# PIR_new.net
KiCad netlist of a schematic drawn in EAGLE
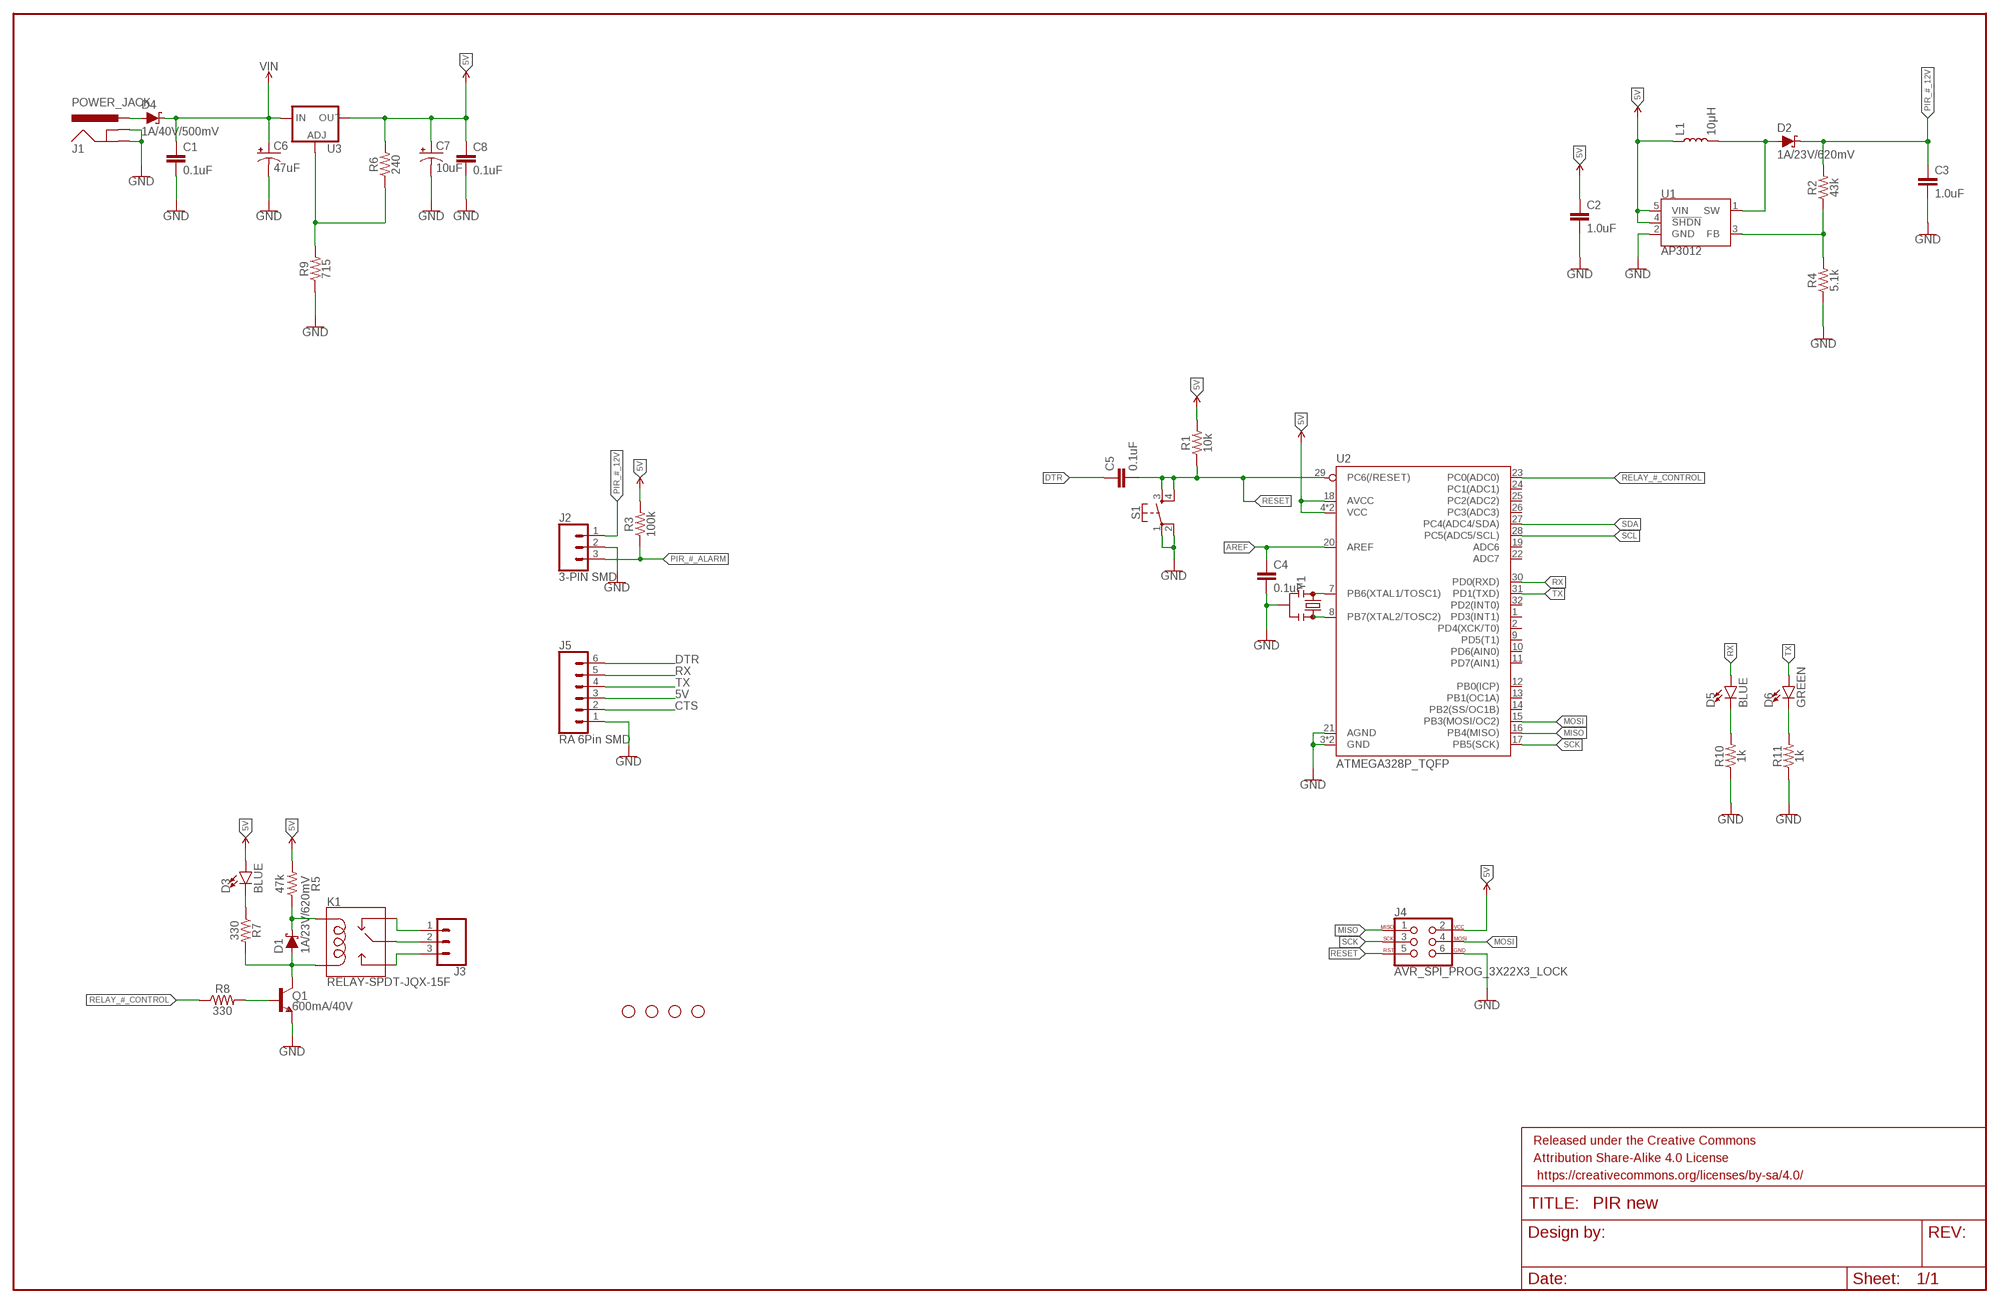
[diagram p0: schematic, sheet 1]

(export (version "E")
  (design (tool "Eeschema 10.0.6"))
  (components
    (comp (ref "C1")
      (value "0.1uF")
      (footprint "eagle-import:0603")
      (libsource (lib "eagle-import") (part "SparkFun-Capacitors_510_0.1UF-0603-25V-5%"))
    )
    (comp (ref "C2")
      (value "1.0uF")
      (footprint "eagle-import:0603")
      (libsource (lib "eagle-import") (part "1.0UF-0603-16V-10%"))
    )
    (comp (ref "C3")
      (value "1.0uF")
      (footprint "eagle-import:0603")
      (libsource (lib "eagle-import") (part "1.0UF-0603-16V-10%"))
    )
    (comp (ref "C4")
      (value "0.1uF")
      (footprint "eagle-import:0603")
      (libsource (lib "eagle-import") (part "0.1UF-0603-25V-(+80/-20%)"))
    )
    (comp (ref "C5")
      (value "0.1uF")
      (footprint "eagle-import:0603")
      (libsource (lib "eagle-import") (part "0.1UF-0603-25V-(+80/-20%)"))
    )
    (comp (ref "C6")
      (value "47uF")
      (footprint "eagle-import:PANASONIC_D")
      (libsource (lib "eagle-import") (part "47UF-POLAR-PANASONIC_D-35V-20%"))
    )
    (comp (ref "C7")
      (value "10uF")
      (footprint "eagle-import:EIA3216")
      (libsource (lib "eagle-import") (part "10UF-POLAR-EIA3216-16V-10%(TANT)"))
    )
    (comp (ref "C8")
      (value "0.1uF")
      (footprint "eagle-import:0603")
      (libsource (lib "eagle-import") (part "0.1UF-0603-25V-(+80/-20%)"))
    )
    (comp (ref "D1")
      (value "1A/23V/620mV")
      (footprint "eagle-import:SOD-323")
      (libsource (lib "eagle-import") (part "DIODE-SCHOTTKY-BAT20J"))
    )
    (comp (ref "D2")
      (value "1A/23V/620mV")
      (footprint "eagle-import:SOD-323")
      (libsource (lib "eagle-import") (part "DIODE-SCHOTTKY-BAT20J"))
    )
    (comp (ref "D3")
      (value "BLUE")
      (footprint "eagle-import:LED-0603")
      (libsource (lib "eagle-import") (part "LED-BLUE0603"))
    )
    (comp (ref "D4")
      (value "1A/40V/500mV")
      (footprint "eagle-import:SMA-DIODE")
      (libsource (lib "eagle-import") (part "DIODE-SCHOTTKY-SS14"))
    )
    (comp (ref "D5")
      (value "BLUE")
      (footprint "eagle-import:LED-0603")
      (libsource (lib "eagle-import") (part "LED-BLUE0603"))
    )
    (comp (ref "D6")
      (value "GREEN")
      (footprint "eagle-import:LED-0603")
      (libsource (lib "eagle-import") (part "LED-GREEN0603"))
    )
    (comp (ref "FRAME1")
      (value "FRAME-LEDGER")
      (footprint "eagle-import:CREATIVE_COMMONS")
      (libsource (lib "eagle-import") (part "FRAME-LEDGER"))
    )
    (comp (ref "H1")
      (value "STAND-OFF")
      (footprint "eagle-import:STAND-OFF")
      (libsource (lib "eagle-import") (part "STAND-OFF"))
    )
    (comp (ref "H2")
      (value "STAND-OFF")
      (footprint "eagle-import:STAND-OFF")
      (libsource (lib "eagle-import") (part "STAND-OFF"))
    )
    (comp (ref "H3")
      (value "STAND-OFF")
      (footprint "eagle-import:STAND-OFF")
      (libsource (lib "eagle-import") (part "STAND-OFF"))
    )
    (comp (ref "H4")
      (value "STAND-OFF")
      (footprint "eagle-import:STAND-OFF")
      (libsource (lib "eagle-import") (part "STAND-OFF"))
    )
    (comp (ref "J1")
      (value "POWER_JACK")
      (footprint "eagle-import:POWER_JACK_PTH")
      (libsource (lib "eagle-import") (part "POWER_JACK"))
    )
    (comp (ref "J2")
      (value "3-PIN SMD")
      (footprint "eagle-import:JST-3-SMD")
      (libsource (lib "eagle-import") (part "CONN_03JST-SMD"))
    )
    (comp (ref "J3")
      (value "CONN_03SCREW_LOCK")
      (footprint "eagle-import:SCREWTERMINAL-3.5MM-3_LOCK.007S")
      (libsource (lib "eagle-import") (part "CONN_03SCREW_LOCK"))
    )
    (comp (ref "J4")
      (value "AVR_SPI_PROG_3X22X3_LOCK")
      (footprint "eagle-import:2X3_LOCK")
      (libsource (lib "eagle-import") (part "AVR_SPI_PROG_3X22X3_LOCK"))
    )
    (comp (ref "J5")
      (value "RA 6Pin SMD")
      (footprint "eagle-import:1X06-SMD_RA_MALE")
      (libsource (lib "eagle-import") (part "CONN_06SMD"))
    )
    (comp (ref "K1")
      (value "RELAY-SPDT-JQX-15F")
      (footprint "eagle-import:RELAY-T90")
      (libsource (lib "eagle-import") (part "RELAY-SPDT-JQX-15F"))
    )
    (comp (ref "L1")
      (value "10μH")
      (footprint "eagle-import:0805")
      (libsource (lib "eagle-import") (part "10μH_SHIELDED_INDUCTOR0805"))
    )
    (comp (ref "Q1")
      (value "600mA/40V")
      (footprint "eagle-import:SOT23-3")
      (libsource (lib "eagle-import") (part "TRANS_NPN-MMBT2222AL"))
    )
    (comp (ref "R1")
      (value "10k")
      (footprint "eagle-import:0603")
      (libsource (lib "eagle-import") (part "10KOHM-0603-1/10W-1%"))
    )
    (comp (ref "R2")
      (value "43k")
      (footprint "eagle-import:0603")
      (libsource (lib "eagle-import") (part "43KOHM-0603-1/10W-1%"))
    )
    (comp (ref "R3")
      (value "100k")
      (footprint "eagle-import:0603")
      (libsource (lib "eagle-import") (part "100KOHM-0603-1/10W-1%"))
    )
    (comp (ref "R4")
      (value "5.1k")
      (footprint "eagle-import:0603")
      (libsource (lib "eagle-import") (part "5.1KOHM5.1KOHM-0603-1/10W-1%"))
    )
    (comp (ref "R5")
      (value "47k")
      (footprint "eagle-import:0603")
      (libsource (lib "eagle-import") (part "47KOHM-0603-1/10W-1%"))
    )
    (comp (ref "R6")
      (value "240")
      (footprint "eagle-import:0603")
      (libsource (lib "eagle-import") (part "240OHM-0603-1/10W-1%"))
    )
    (comp (ref "R7")
      (value "330")
      (footprint "eagle-import:0603")
      (libsource (lib "eagle-import") (part "330OHM-0603-1/10W-1%"))
    )
    (comp (ref "R8")
      (value "330")
      (footprint "eagle-import:0603")
      (libsource (lib "eagle-import") (part "330OHM-0603-1/10W-1%"))
    )
    (comp (ref "R9")
      (value "715")
      (footprint "eagle-import:0603")
      (libsource (lib "eagle-import") (part "715OHM-0603-1/10W-1%"))
    )
    (comp (ref "R10")
      (value "1k")
      (footprint "eagle-import:0603")
      (libsource (lib "eagle-import") (part "1KOHM-0603-1/10W-1%"))
    )
    (comp (ref "R11")
      (value "1k")
      (footprint "eagle-import:0603")
      (libsource (lib "eagle-import") (part "1KOHM-0603-1/10W-1%"))
    )
    (comp (ref "S1")
      (value "MOMENTARY-SWITCH-SPST-2-SMD-5.2MM-TALL")
      (footprint "eagle-import:TACTILE_SWITCH_SMD_5.2MM")
      (libsource (lib "eagle-import") (part "MOMENTARY-SWITCH-SPST-2-SMD-5.2MM-TALL"))
    )
    (comp (ref "U1")
      (value "AP3012")
      (footprint "eagle-import:SOT23-5")
      (libsource (lib "eagle-import") (part "AP3012"))
    )
    (comp (ref "U2")
      (value "ATMEGA328P_TQFP")
      (footprint "eagle-import:TQFP32-08")
      (libsource (lib "eagle-import") (part "ATMEGA328P_TQFP"))
    )
    (comp (ref "U3")
      (value "V_REG_LM1117SOT223")
      (footprint "eagle-import:SOT223")
      (libsource (lib "eagle-import") (part "V_REG_LM1117SOT223"))
    )
    (comp (ref "Y1")
      (value "RESONATORSMD-3.2X1.3")
      (footprint "eagle-import:RESONATOR-SMD-3.2X1.3")
      (libsource (lib "eagle-import") (part "RESONATORSMD-3.2X1.3"))
    )
  )
  (nets
    (net (code "1") (name "/CTS") (class "Default")
      (node (ref "J5") (pin "2") (pinfunction "2_2") (pintype "passive"))
    )
    (net (code "2") (name "5V") (class "Default")
      (node (ref "C2") (pin "1") (pinfunction "1_1") (pintype "passive"))
      (node (ref "C7") (pin "+") (pinfunction "+_+") (pintype "passive"))
      (node (ref "C8") (pin "1") (pinfunction "1_1") (pintype "passive"))
      (node (ref "D3") (pin "A") (pinfunction "A_A") (pintype "passive"))
      (node (ref "J4") (pin "2") (pinfunction "2_2") (pintype "passive"))
      (node (ref "J5") (pin "3") (pinfunction "3_3") (pintype "passive"))
      (node (ref "L1") (pin "1") (pinfunction "1_1") (pintype "passive"))
      (node (ref "R1") (pin "2") (pinfunction "2_2") (pintype "passive"))
      (node (ref "R3") (pin "2") (pinfunction "2_2") (pintype "passive"))
      (node (ref "R5") (pin "2") (pinfunction "2_2") (pintype "passive"))
      (node (ref "R6") (pin "2") (pinfunction "2_2") (pintype "passive"))
      (node (ref "U1") (pin "4") (pinfunction "~{SHDN}_4") (pintype "bidirectional"))
      (node (ref "U1") (pin "5") (pinfunction "VIN_5") (pintype "bidirectional"))
      (node (ref "U2") (pin "18") (pinfunction "AVCC_18") (pintype "bidirectional"))
      (node (ref "U2") (pin "4") (pinfunction "VCC_4") (pintype "bidirectional"))
      (node (ref "U2") (pin "6") (pinfunction "VCC_6") (pintype "bidirectional"))
      (node (ref "U3") (pin "2") (pinfunction "OUT_2") (pintype "output"))
      (node (ref "U3") (pin "4") (pinfunction "OUT_4") (pintype "output"))
    )
    (net (code "3") (name "AREF") (class "Default")
      (node (ref "C4") (pin "1") (pinfunction "1_1") (pintype "passive"))
      (node (ref "U2") (pin "20") (pinfunction "AREF_20") (pintype "bidirectional"))
    )
    (net (code "4") (name "DTR") (class "Default")
      (node (ref "C5") (pin "1") (pinfunction "1_1") (pintype "passive"))
      (node (ref "J5") (pin "6") (pinfunction "6_6") (pintype "passive"))
    )
    (net (code "5") (name "GND") (class "Default")
      (node (ref "C1") (pin "2") (pinfunction "2_2") (pintype "passive"))
      (node (ref "C2") (pin "2") (pinfunction "2_2") (pintype "passive"))
      (node (ref "C3") (pin "2") (pinfunction "2_2") (pintype "passive"))
      (node (ref "C4") (pin "2") (pinfunction "2_2") (pintype "passive"))
      (node (ref "C6") (pin "-") (pinfunction "-_-") (pintype "passive"))
      (node (ref "C7") (pin "-") (pinfunction "-_-") (pintype "passive"))
      (node (ref "C8") (pin "2") (pinfunction "2_2") (pintype "passive"))
      (node (ref "J1") (pin "GND") (pinfunction "GND_GND") (pintype "bidirectional"))
      (node (ref "J1") (pin "GNDBREAK") (pinfunction "GNDBREAK_GNDBREAK") (pintype "bidirectional"))
      (node (ref "J2") (pin "2") (pinfunction "2_2") (pintype "passive"))
      (node (ref "J4") (pin "6") (pinfunction "6_6") (pintype "passive"))
      (node (ref "J5") (pin "1") (pinfunction "1_1") (pintype "passive"))
      (node (ref "Q1") (pin "2") (pinfunction "E_2") (pintype "passive"))
      (node (ref "R10") (pin "1") (pinfunction "1_1") (pintype "passive"))
      (node (ref "R11") (pin "1") (pinfunction "1_1") (pintype "passive"))
      (node (ref "R4") (pin "1") (pinfunction "1_1") (pintype "passive"))
      (node (ref "R9") (pin "1") (pinfunction "1_1") (pintype "passive"))
      (node (ref "S1") (pin "1") (pinfunction "1_1") (pintype "passive"))
      (node (ref "S1") (pin "2") (pinfunction "2_2") (pintype "passive"))
      (node (ref "U1") (pin "2") (pinfunction "GND_2") (pintype "bidirectional"))
      (node (ref "U2") (pin "21") (pinfunction "AGND_21") (pintype "bidirectional"))
      (node (ref "U2") (pin "3") (pinfunction "GND_3") (pintype "bidirectional"))
      (node (ref "U2") (pin "5") (pinfunction "GND_5") (pintype "bidirectional"))
      (node (ref "Y1") (pin "2") (pinfunction "2_2") (pintype "passive"))
    )
    (net (code "6") (name "MISO") (class "Default")
      (node (ref "J4") (pin "1") (pinfunction "1_1") (pintype "passive"))
      (node (ref "U2") (pin "16") (pinfunction "PB4(MISO)_16") (pintype "bidirectional"))
    )
    (net (code "7") (name "MOSI") (class "Default")
      (node (ref "J4") (pin "4") (pinfunction "4_4") (pintype "passive"))
      (node (ref "U2") (pin "15") (pinfunction "PB3(MOSI/OC2)_15") (pintype "bidirectional"))
    )
    (net (code "8") (name "Net-(D1-PadC)") (class "Default")
      (node (ref "D1") (pin "C") (pinfunction "C_C") (pintype "passive"))
      (node (ref "K1") (pin "COIL1") (pinfunction "COIL1_COIL1") (pintype "bidirectional"))
      (node (ref "R5") (pin "1") (pinfunction "1_1") (pintype "passive"))
    )
    (net (code "9") (name "Net-(D3-PadC)") (class "Default")
      (node (ref "D3") (pin "C") (pinfunction "C_C") (pintype "passive"))
      (node (ref "R7") (pin "1") (pinfunction "1_1") (pintype "passive"))
    )
    (net (code "10") (name "Net-(D4-PadA)") (class "Default")
      (node (ref "D4") (pin "A") (pinfunction "A_A") (pintype "passive"))
      (node (ref "J1") (pin "PWR") (pinfunction "PWR_PWR") (pintype "bidirectional"))
    )
    (net (code "11") (name "Net-(D5-PadC)") (class "Default")
      (node (ref "D5") (pin "C") (pinfunction "C_C") (pintype "passive"))
      (node (ref "R10") (pin "2") (pinfunction "2_2") (pintype "passive"))
    )
    (net (code "12") (name "Net-(D6-PadC)") (class "Default")
      (node (ref "D6") (pin "C") (pinfunction "C_C") (pintype "passive"))
      (node (ref "R11") (pin "2") (pinfunction "2_2") (pintype "passive"))
    )
    (net (code "13") (name "Net-(J3-Pad1)") (class "Default")
      (node (ref "J3") (pin "1") (pinfunction "1_1") (pintype "passive"))
      (node (ref "K1") (pin "NC") (pinfunction "NC_NC") (pintype "bidirectional"))
    )
    (net (code "14") (name "Net-(J3-Pad2)") (class "Default")
      (node (ref "J3") (pin "2") (pinfunction "2_2") (pintype "passive"))
      (node (ref "K1") (pin "MAIN") (pinfunction "MAIN_MAIN") (pintype "bidirectional"))
    )
    (net (code "15") (name "Net-(J3-Pad3)") (class "Default")
      (node (ref "J3") (pin "3") (pinfunction "3_3") (pintype "passive"))
      (node (ref "K1") (pin "NO") (pinfunction "NO_NO") (pintype "bidirectional"))
    )
    (net (code "16") (name "Net-(Q1-B)") (class "Default")
      (node (ref "Q1") (pin "1") (pinfunction "B_1") (pintype "passive"))
      (node (ref "R8") (pin "2") (pinfunction "2_2") (pintype "passive"))
    )
    (net (code "17") (name "Net-(Q1-C)") (class "Default")
      (node (ref "D1") (pin "A") (pinfunction "A_A") (pintype "passive"))
      (node (ref "K1") (pin "COIL2") (pinfunction "COIL2_COIL2") (pintype "bidirectional"))
      (node (ref "Q1") (pin "3") (pinfunction "C_3") (pintype "passive"))
      (node (ref "R7") (pin "2") (pinfunction "2_2") (pintype "passive"))
    )
    (net (code "18") (name "Net-(U1-FB)") (class "Default")
      (node (ref "R2") (pin "1") (pinfunction "1_1") (pintype "passive"))
      (node (ref "R4") (pin "2") (pinfunction "2_2") (pintype "passive"))
      (node (ref "U1") (pin "3") (pinfunction "FB_3") (pintype "bidirectional"))
    )
    (net (code "19") (name "Net-(U1-SW)") (class "Default")
      (node (ref "D2") (pin "A") (pinfunction "A_A") (pintype "passive"))
      (node (ref "L1") (pin "2") (pinfunction "2_2") (pintype "passive"))
      (node (ref "U1") (pin "1") (pinfunction "SW_1") (pintype "bidirectional"))
    )
    (net (code "20") (name "Net-(U2-PB6(XTAL1{slash}TOSC1))") (class "Default")
      (node (ref "U2") (pin "7") (pinfunction "PB6(XTAL1/TOSC1)_7") (pintype "bidirectional"))
      (node (ref "Y1") (pin "1") (pinfunction "1_1") (pintype "passive"))
    )
    (net (code "21") (name "Net-(U2-PB7(XTAL2{slash}TOSC2))") (class "Default")
      (node (ref "U2") (pin "8") (pinfunction "PB7(XTAL2/TOSC2)_8") (pintype "bidirectional"))
      (node (ref "Y1") (pin "3") (pinfunction "3_3") (pintype "passive"))
    )
    (net (code "22") (name "Net-(U3-ADJ)") (class "Default")
      (node (ref "R6") (pin "1") (pinfunction "1_1") (pintype "passive"))
      (node (ref "R9") (pin "2") (pinfunction "2_2") (pintype "passive"))
      (node (ref "U3") (pin "1") (pinfunction "ADJ_1") (pintype "input"))
    )
    (net (code "23") (name "PIR_#_12V") (class "Default")
      (node (ref "C3") (pin "1") (pinfunction "1_1") (pintype "passive"))
      (node (ref "D2") (pin "C") (pinfunction "C_C") (pintype "passive"))
      (node (ref "J2") (pin "1") (pinfunction "3_1") (pintype "passive"))
      (node (ref "R2") (pin "2") (pinfunction "2_2") (pintype "passive"))
    )
    (net (code "24") (name "PIR_#_ALARM") (class "Default")
      (node (ref "J2") (pin "3") (pinfunction "1_3") (pintype "passive"))
      (node (ref "R3") (pin "1") (pinfunction "1_1") (pintype "passive"))
    )
    (net (code "25") (name "RELAY_#_CONTROL") (class "Default")
      (node (ref "R8") (pin "1") (pinfunction "1_1") (pintype "passive"))
      (node (ref "U2") (pin "23") (pinfunction "PC0(ADC0)_23") (pintype "bidirectional"))
    )
    (net (code "26") (name "RESET") (class "Default")
      (node (ref "C5") (pin "2") (pinfunction "2_2") (pintype "passive"))
      (node (ref "J4") (pin "5") (pinfunction "5_5") (pintype "passive"))
      (node (ref "R1") (pin "1") (pinfunction "1_1") (pintype "passive"))
      (node (ref "S1") (pin "3") (pinfunction "3_3") (pintype "passive"))
      (node (ref "S1") (pin "4") (pinfunction "4_4") (pintype "passive"))
      (node (ref "U2") (pin "29") (pinfunction "PC6(/RESET)_29") (pintype "bidirectional"))
    )
    (net (code "27") (name "RX") (class "Default")
      (node (ref "D5") (pin "A") (pinfunction "A_A") (pintype "passive"))
      (node (ref "J5") (pin "5") (pinfunction "5_5") (pintype "passive"))
      (node (ref "U2") (pin "30") (pinfunction "PD0(RXD)_30") (pintype "bidirectional"))
    )
    (net (code "28") (name "SCK") (class "Default")
      (node (ref "J4") (pin "3") (pinfunction "3_3") (pintype "passive"))
      (node (ref "U2") (pin "17") (pinfunction "PB5(SCK)_17") (pintype "bidirectional"))
    )
    (net (code "29") (name "SCL") (class "Default")
      (node (ref "U2") (pin "28") (pinfunction "PC5(ADC5/SCL)_28") (pintype "bidirectional"))
    )
    (net (code "30") (name "SDA") (class "Default")
      (node (ref "U2") (pin "27") (pinfunction "PC4(ADC4/SDA)_27") (pintype "bidirectional"))
    )
    (net (code "31") (name "TX") (class "Default")
      (node (ref "D6") (pin "A") (pinfunction "A_A") (pintype "passive"))
      (node (ref "J5") (pin "4") (pinfunction "4_4") (pintype "passive"))
      (node (ref "U2") (pin "31") (pinfunction "PD1(TXD)_31") (pintype "bidirectional"))
    )
    (net (code "32") (name "VIN") (class "Default")
      (node (ref "C1") (pin "1") (pinfunction "1_1") (pintype "passive"))
      (node (ref "C6") (pin "+") (pinfunction "+_+") (pintype "passive"))
      (node (ref "D4") (pin "C") (pinfunction "C_C") (pintype "passive"))
      (node (ref "U3") (pin "3") (pinfunction "IN_3") (pintype "input"))
    )
    (net (code "33") (name "unconnected-(U2-ADC6-Pad19)") (class "Default")
      (node (ref "U2") (pin "19") (pinfunction "ADC6_19") (pintype "bidirectional"))
    )
    (net (code "34") (name "unconnected-(U2-ADC7-Pad22)") (class "Default")
      (node (ref "U2") (pin "22") (pinfunction "ADC7_22") (pintype "bidirectional"))
    )
    (net (code "35") (name "unconnected-(U2-PB0(ICP)-Pad12)") (class "Default")
      (node (ref "U2") (pin "12") (pinfunction "PB0(ICP)_12") (pintype "bidirectional"))
    )
    (net (code "36") (name "unconnected-(U2-PB1(OC1A)-Pad13)") (class "Default")
      (node (ref "U2") (pin "13") (pinfunction "PB1(OC1A)_13") (pintype "bidirectional"))
    )
    (net (code "37") (name "unconnected-(U2-PB2(SS{slash}OC1B)-Pad14)") (class "Default")
      (node (ref "U2") (pin "14") (pinfunction "PB2(SS/OC1B)_14") (pintype "bidirectional"))
    )
    (net (code "38") (name "unconnected-(U2-PC1(ADC1)-Pad24)") (class "Default")
      (node (ref "U2") (pin "24") (pinfunction "PC1(ADC1)_24") (pintype "bidirectional"))
    )
    (net (code "39") (name "unconnected-(U2-PC2(ADC2)-Pad25)") (class "Default")
      (node (ref "U2") (pin "25") (pinfunction "PC2(ADC2)_25") (pintype "bidirectional"))
    )
    (net (code "40") (name "unconnected-(U2-PC3(ADC3)-Pad26)") (class "Default")
      (node (ref "U2") (pin "26") (pinfunction "PC3(ADC3)_26") (pintype "bidirectional"))
    )
    (net (code "41") (name "unconnected-(U2-PD2(INT0)-Pad32)") (class "Default")
      (node (ref "U2") (pin "32") (pinfunction "PD2(INT0)_32") (pintype "bidirectional"))
    )
    (net (code "42") (name "unconnected-(U2-PD3(INT1)-Pad1)") (class "Default")
      (node (ref "U2") (pin "1") (pinfunction "PD3(INT1)_1") (pintype "bidirectional"))
    )
    (net (code "43") (name "unconnected-(U2-PD4(XCK{slash}T0)-Pad2)") (class "Default")
      (node (ref "U2") (pin "2") (pinfunction "PD4(XCK/T0)_2") (pintype "bidirectional"))
    )
    (net (code "44") (name "unconnected-(U2-PD5(T1)-Pad9)") (class "Default")
      (node (ref "U2") (pin "9") (pinfunction "PD5(T1)_9") (pintype "bidirectional"))
    )
    (net (code "45") (name "unconnected-(U2-PD6(AIN0)-Pad10)") (class "Default")
      (node (ref "U2") (pin "10") (pinfunction "PD6(AIN0)_10") (pintype "bidirectional"))
    )
    (net (code "46") (name "unconnected-(U2-PD7(AIN1)-Pad11)") (class "Default")
      (node (ref "U2") (pin "11") (pinfunction "PD7(AIN1)_11") (pintype "bidirectional"))
    )
  )
)
